# MCU.net
KiCad netlist of a schematic drawn in Altium Designer
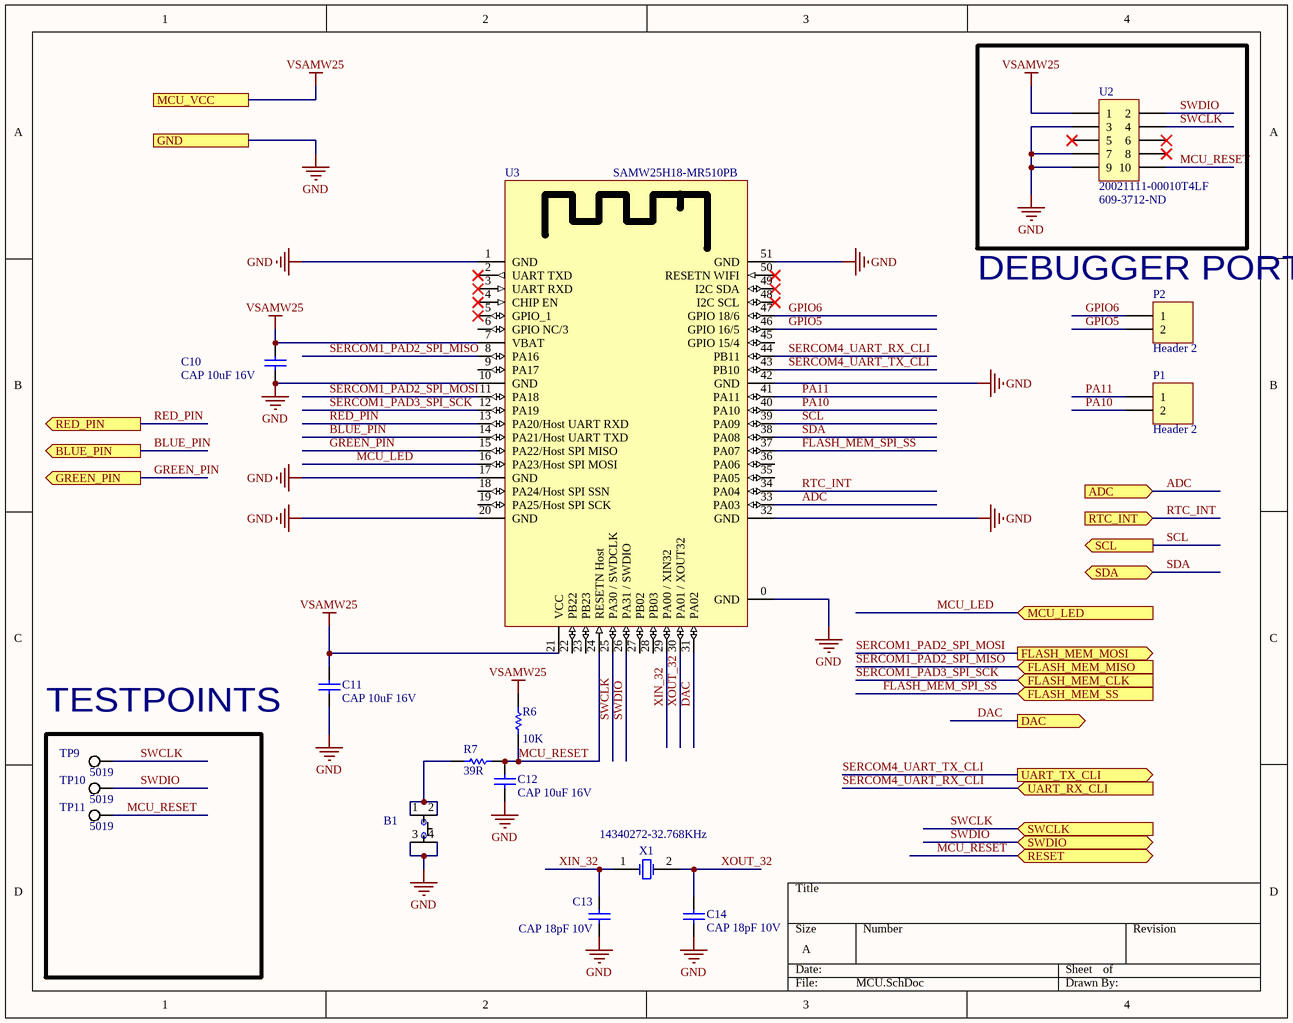
[diagram p0: MCU.SchDoc]

(export (version "E")
  (design (tool "Eeschema 10.0.6"))
  (components
    (comp (ref "B1")
      (value "PTS810 SJK 250 SMTR LFS")
      (footprint "PTS810 SJK 250 SMTR LFS")
      (description "SWITCH TACTILE SPST-NO 0.05A 16V Tactile Switch SPST-NO Top Actuated Surface Mount")
      (fields
        (field (name "MANUFACTURER") "ITT /  C&K Components")
        (field (name "MANUFACTURER PART NUMBER") "PTS810SJK250SMTRLFS")
      )
      (libsource (lib "Schematics") (part "PTS810 SJK 250 SMTR LFS"))
    )
    (comp (ref "C10")
      (value "CAP 10uF 16V")
      (footprint "CAPC0805(2012)145_L")
      (description "CAP 10uF 16V ±10% 0805 (2012 Metric) Thickness 1.45mm SMD")
      (fields (field (name "TOLERANCE") "Â±10%"))
      (libsource (lib "Altium Content Vault") (part "CAP"))
    )
    (comp (ref "C11")
      (value "CAP 10uF 16V")
      (footprint "CAPC0805(2012)145_L")
      (description "CAP 10uF 16V ±10% 0805 (2012 Metric) Thickness 1.45mm SMD")
      (fields (field (name "TOLERANCE") "Â±10%"))
      (libsource (lib "Altium Content Vault") (part "CAP"))
    )
    (comp (ref "C12")
      (value "CAP 10uF 16V")
      (footprint "CAPC0805(2012)145_L")
      (description "CAP 10uF 16V ±10% 0805 (2012 Metric) Thickness 1.45mm SMD")
      (fields (field (name "TOLERANCE") "Â±10%"))
      (libsource (lib "Altium Content Vault") (part "CAP"))
    )
    (comp (ref "C13")
      (value "CAP 18pF 10V")
      (footprint "CAPC0805(2012)75_L")
      (description "CAP 18pF 10V ±1% 0805 (2012 Metric) Thickness 0.75mm SMD")
      (fields (field (name "TOLERANCE") "Â±1%"))
      (libsource (lib "Altium Content Vault") (part "CAP"))
    )
    (comp (ref "C14")
      (value "CAP 18pF 10V")
      (footprint "CAPC0805(2012)75_L")
      (description "CAP 18pF 10V ±1% 0805 (2012 Metric) Thickness 0.75mm SMD")
      (fields (field (name "TOLERANCE") "Â±1%"))
      (libsource (lib "Altium Content Vault") (part "CAP"))
    )
    (comp (ref "P1")
      (value "Header 2")
      (footprint "HDR1X2")
      (description "Header, 2-Pin")
      (fields (field (name "PUBLISHER") "Altium Limited"))
      (libsource (lib "Miscellaneous Connectors") (part "Header 2"))
    )
    (comp (ref "P2")
      (value "Header 2")
      (footprint "HDR1X2")
      (description "Header, 2-Pin")
      (fields (field (name "PUBLISHER") "Altium Limited"))
      (libsource (lib "Miscellaneous Connectors") (part "Header 2"))
    )
    (comp (ref "R6")
      (value "10K")
      (footprint "J1-0603")
      (description "Resistor")
      (fields (field (name "PUBLISHER") "Altium Limited"))
      (libsource (lib "Miscellaneous Devices") (part "Res1"))
    )
    (comp (ref "R7")
      (value "39R")
      (footprint "RESC0805(2012)_N")
      (description "39R 0.125W 5% 0805 (2012 Metric)  SMD")
      (fields (field (name "POWER") "0.125 W") (field (name "TOLERANCE") "5 %"))
      (libsource (lib "Altium Content Vault") (part "RES"))
    )
    (comp (ref "TP9")
      (value "5019")
      (footprint "KSTN-5019_V")
      (description "Test Point, 1 Position SMD, RoHS, Tape and Reel")
      (libsource (lib "Altium Content Vault") (part "TESTPOINT_WHITE"))
    )
    (comp (ref "TP10")
      (value "5019")
      (footprint "KSTN-5019_V")
      (description "Test Point, 1 Position SMD, RoHS, Tape and Reel")
      (libsource (lib "Altium Content Vault") (part "TESTPOINT_WHITE"))
    )
    (comp (ref "TP11")
      (value "5019")
      (footprint "KSTN-5019_V")
      (description "Test Point, 1 Position SMD, RoHS, Tape and Reel")
      (libsource (lib "Altium Content Vault") (part "TESTPOINT_WHITE"))
    )
    (comp (ref "U2")
      (value "20021111-00010T4LF")
      (footprint "20021111-00010T4LF")
      (description "CONN HEADER 10POS UNSHD VERT T/H")
      (fields
        (field (name "MANUFACTURER") "Amphenol / FCI")
        (field (name "SUPPLIER PART NUMBER 1") "609-3712-ND")
      )
      (libsource (lib "Schematics") (part "20021111-00010T4LF"))
    )
    (comp (ref "U3")
      (value "SAMW25H18-MR510PB")
      (footprint "SAMW25H18-MR510PB")
      (description "RF TXRX MODULE WIFI TRACE ANT")
      (fields
        (field (name "MANUFACTURER") "Atmel")
        (field (name "MANUFACTURER PART NUMBER") "ATSAMW25H18-MR510PB")
      )
      (libsource (lib "Schematics") (part "SAMW25H18-MR510PB"))
    )
    (comp (ref "X1")
      (value "14340272-32.768KHz")
      (footprint "ITTI-14340272-32.768KHz-2_V")
      (description "Crystal, 32.768 KHz, -40 to 85 degC, 3.2 x 1.5 x 0.9 mm SMD")
      (fields (field (name "MANUFACTURER") "ITTI"))
      (libsource (lib "Altium Content Vault") (part "ITTI-14340272-2"))
    )
  )
  (nets
    (net (code "1") (name "/ADC") (class "Default")
      (node (ref "U3") (pin "33") (pinfunction "PA03_33") (pintype "bidirectional"))
    )
    (net (code "2") (name "/BLUE_PIN") (class "Default")
      (node (ref "U3") (pin "14") (pinfunction "PA21/Host_UART_TXD_14") (pintype "bidirectional"))
    )
    (net (code "3") (name "/DAC") (class "Default")
      (node (ref "U3") (pin "31") (pinfunction "PA02_31") (pintype "bidirectional"))
    )
    (net (code "4") (name "/FLASH_MEM_SPI_SS") (class "Default")
      (node (ref "U3") (pin "37") (pinfunction "PA07_37") (pintype "bidirectional"))
    )
    (net (code "5") (name "/GPIO5") (class "Default")
      (node (ref "P2") (pin "2") (pinfunction "2_2") (pintype "passive"))
      (node (ref "U3") (pin "46") (pinfunction "GPIO_16/5_46") (pintype "bidirectional"))
    )
    (net (code "6") (name "/GPIO6") (class "Default")
      (node (ref "P2") (pin "1") (pinfunction "1_1") (pintype "passive"))
      (node (ref "U3") (pin "47") (pinfunction "GPIO_18/6_47") (pintype "bidirectional"))
    )
    (net (code "7") (name "/GREEN_PIN") (class "Default")
      (node (ref "U3") (pin "15") (pinfunction "PA22/Host_SPI_MISO_15") (pintype "bidirectional"))
    )
    (net (code "8") (name "/MCU_LED") (class "Default")
      (node (ref "U3") (pin "16") (pinfunction "PA23/Host_SPI_MOSI_16") (pintype "bidirectional"))
    )
    (net (code "9") (name "/MCU_RESET") (class "Default")
      (node (ref "C12") (pin "2") (pinfunction "2_2") (pintype "passive"))
      (node (ref "R6") (pin "1") (pinfunction "1_1") (pintype "passive"))
      (node (ref "R7") (pin "1") (pinfunction "1_1") (pintype "passive"))
      (node (ref "TP11") (pin "1") (pinfunction "1_1") (pintype "passive"))
      (node (ref "U2") (pin "10") (pinfunction "10_10") (pintype "passive"))
      (node (ref "U3") (pin "24") (pinfunction "RESETN_Host_24") (pintype "input"))
    )
    (net (code "10") (name "/PA10") (class "Default")
      (node (ref "P1") (pin "2") (pinfunction "2_2") (pintype "passive"))
      (node (ref "U3") (pin "40") (pinfunction "PA10_40") (pintype "bidirectional"))
    )
    (net (code "11") (name "/PA11") (class "Default")
      (node (ref "P1") (pin "1") (pinfunction "1_1") (pintype "passive"))
      (node (ref "U3") (pin "41") (pinfunction "PA11_41") (pintype "bidirectional"))
    )
    (net (code "12") (name "/RED_PIN") (class "Default")
      (node (ref "U3") (pin "13") (pinfunction "PA20/Host_UART_RXD_13") (pintype "bidirectional"))
    )
    (net (code "13") (name "/RTC_INT") (class "Default")
      (node (ref "U3") (pin "34") (pinfunction "PA04_34") (pintype "bidirectional"))
    )
    (net (code "14") (name "/SCL") (class "Default")
      (node (ref "U3") (pin "39") (pinfunction "PA09_39") (pintype "bidirectional"))
    )
    (net (code "15") (name "/SDA") (class "Default")
      (node (ref "U3") (pin "38") (pinfunction "PA08_38") (pintype "bidirectional"))
    )
    (net (code "16") (name "/SERCOM1_PAD2_SPI_MISO") (class "Default")
      (node (ref "U3") (pin "8") (pinfunction "PA16_8") (pintype "bidirectional"))
    )
    (net (code "17") (name "/SERCOM1_PAD2_SPI_MOSI") (class "Default")
      (node (ref "U3") (pin "11") (pinfunction "PA18_11") (pintype "bidirectional"))
    )
    (net (code "18") (name "/SERCOM1_PAD3_SPI_SCK") (class "Default")
      (node (ref "U3") (pin "12") (pinfunction "PA19_12") (pintype "bidirectional"))
    )
    (net (code "19") (name "/SERCOM4_UART_RX_CLI") (class "Default")
      (node (ref "U3") (pin "44") (pinfunction "PB11_44") (pintype "bidirectional"))
    )
    (net (code "20") (name "/SERCOM4_UART_TX_CLI") (class "Default")
      (node (ref "U3") (pin "43") (pinfunction "PB10_43") (pintype "bidirectional"))
    )
    (net (code "21") (name "/SWCLK") (class "Default")
      (node (ref "TP9") (pin "1") (pinfunction "1_1") (pintype "passive"))
      (node (ref "U2") (pin "4") (pinfunction "4_4") (pintype "passive"))
      (node (ref "U3") (pin "25") (pinfunction "PA30_/_SWDCLK_25") (pintype "bidirectional"))
    )
    (net (code "22") (name "/SWDIO") (class "Default")
      (node (ref "TP10") (pin "1") (pinfunction "1_1") (pintype "passive"))
      (node (ref "U2") (pin "2") (pinfunction "2_2") (pintype "passive"))
      (node (ref "U3") (pin "26") (pinfunction "PA31_/_SWDIO_26") (pintype "bidirectional"))
    )
    (net (code "23") (name "/XIN_32") (class "Default")
      (node (ref "C13") (pin "1") (pinfunction "1_1") (pintype "passive"))
      (node (ref "U3") (pin "29") (pinfunction "PA00_/_XIN32_29") (pintype "bidirectional"))
      (node (ref "X1") (pin "1") (pinfunction "X1_1") (pintype "passive"))
    )
    (net (code "24") (name "/XOUT_32") (class "Default")
      (node (ref "C14") (pin "1") (pinfunction "1_1") (pintype "passive"))
      (node (ref "U3") (pin "30") (pinfunction "PA01_/_XOUT32_30") (pintype "bidirectional"))
      (node (ref "X1") (pin "2") (pinfunction "X2_2") (pintype "passive"))
    )
    (net (code "25") (name "GND") (class "Default")
      (node (ref "B1") (pin "3") (pinfunction "3_3") (pintype "power_in"))
      (node (ref "B1") (pin "4") (pinfunction "4_4") (pintype "power_in"))
      (node (ref "C10") (pin "1") (pinfunction "1_1") (pintype "passive"))
      (node (ref "C11") (pin "1") (pinfunction "1_1") (pintype "passive"))
      (node (ref "C12") (pin "1") (pinfunction "1_1") (pintype "passive"))
      (node (ref "C13") (pin "2") (pinfunction "2_2") (pintype "passive"))
      (node (ref "C14") (pin "2") (pinfunction "2_2") (pintype "passive"))
      (node (ref "U2") (pin "3") (pinfunction "3_3") (pintype "passive"))
      (node (ref "U2") (pin "7") (pinfunction "7_7") (pintype "passive"))
      (node (ref "U2") (pin "9") (pinfunction "9_9") (pintype "passive"))
      (node (ref "U3") (pin "0") (pinfunction "GND_0") (pintype "power_in"))
      (node (ref "U3") (pin "1") (pinfunction "GND_1") (pintype "power_in"))
      (node (ref "U3") (pin "10") (pinfunction "GND_10") (pintype "power_in"))
      (node (ref "U3") (pin "17") (pinfunction "GND_17") (pintype "power_in"))
      (node (ref "U3") (pin "20") (pinfunction "GND_20") (pintype "power_in"))
      (node (ref "U3") (pin "32") (pinfunction "GND_32") (pintype "power_in"))
      (node (ref "U3") (pin "42") (pinfunction "GND_42") (pintype "power_in"))
      (node (ref "U3") (pin "51") (pinfunction "GND_51") (pintype "power_in"))
    )
    (net (code "26") (name "Net-(B1-Pad1)") (class "Default")
      (node (ref "B1") (pin "1") (pinfunction "1_1") (pintype "power_in"))
      (node (ref "B1") (pin "2") (pinfunction "2_2") (pintype "power_in"))
      (node (ref "R7") (pin "2") (pinfunction "2_2") (pintype "passive"))
    )
    (net (code "27") (name "VSAMW25") (class "Default")
      (node (ref "C10") (pin "2") (pinfunction "2_2") (pintype "passive"))
      (node (ref "C11") (pin "2") (pinfunction "2_2") (pintype "passive"))
      (node (ref "R6") (pin "2") (pinfunction "2_2") (pintype "passive"))
      (node (ref "U2") (pin "1") (pinfunction "1_1") (pintype "passive"))
      (node (ref "U3") (pin "21") (pinfunction "VCC_21") (pintype "power_in"))
      (node (ref "U3") (pin "7") (pinfunction "VBAT_7") (pintype "power_in"))
    )
    (net (code "28") (name "unconnected-(U2-Pad5)") (class "Default")
      (node (ref "U2") (pin "5") (pinfunction "5_5") (pintype "passive+no_connect"))
    )
    (net (code "29") (name "unconnected-(U2-Pad6)") (class "Default")
      (node (ref "U2") (pin "6") (pinfunction "6_6") (pintype "passive+no_connect"))
    )
    (net (code "30") (name "unconnected-(U2-Pad8)") (class "Default")
      (node (ref "U2") (pin "8") (pinfunction "8_8") (pintype "passive+no_connect"))
    )
    (net (code "31") (name "unconnected-(U3-CHIP_EN-Pad4)") (class "Default")
      (node (ref "U3") (pin "4") (pinfunction "CHIP_EN_4") (pintype "input+no_connect"))
    )
    (net (code "32") (name "unconnected-(U3-GPIO_1-Pad5)") (class "Default")
      (node (ref "U3") (pin "5") (pinfunction "GPIO_1_5") (pintype "bidirectional+no_connect"))
    )
    (net (code "33") (name "unconnected-(U3-GPIO_15{slash}4-Pad45)") (class "Default")
      (node (ref "U3") (pin "45") (pinfunction "GPIO_15/4_45") (pintype "bidirectional"))
    )
    (net (code "34") (name "unconnected-(U3-GPIO_NC{slash}3-Pad6)") (class "Default")
      (node (ref "U3") (pin "6") (pinfunction "GPIO_NC/3_6") (pintype "bidirectional"))
    )
    (net (code "35") (name "unconnected-(U3-I2C_SCL-Pad48)") (class "Default")
      (node (ref "U3") (pin "48") (pinfunction "I2C_SCL_48") (pintype "bidirectional+no_connect"))
    )
    (net (code "36") (name "unconnected-(U3-I2C_SDA-Pad49)") (class "Default")
      (node (ref "U3") (pin "49") (pinfunction "I2C_SDA_49") (pintype "bidirectional+no_connect"))
    )
    (net (code "37") (name "unconnected-(U3-PA05-Pad35)") (class "Default")
      (node (ref "U3") (pin "35") (pinfunction "PA05_35") (pintype "bidirectional"))
    )
    (net (code "38") (name "unconnected-(U3-PA06-Pad36)") (class "Default")
      (node (ref "U3") (pin "36") (pinfunction "PA06_36") (pintype "bidirectional"))
    )
    (net (code "39") (name "unconnected-(U3-PA17-Pad9)") (class "Default")
      (node (ref "U3") (pin "9") (pinfunction "PA17_9") (pintype "bidirectional"))
    )
    (net (code "40") (name "unconnected-(U3-PA24{slash}Host_SPI_SSN-Pad18)") (class "Default")
      (node (ref "U3") (pin "18") (pinfunction "PA24/Host_SPI_SSN_18") (pintype "bidirectional"))
    )
    (net (code "41") (name "unconnected-(U3-PA25{slash}Host_SPI_SCK-Pad19)") (class "Default")
      (node (ref "U3") (pin "19") (pinfunction "PA25/Host_SPI_SCK_19") (pintype "bidirectional"))
    )
    (net (code "42") (name "unconnected-(U3-PB02-Pad27)") (class "Default")
      (node (ref "U3") (pin "27") (pinfunction "PB02_27") (pintype "bidirectional"))
    )
    (net (code "43") (name "unconnected-(U3-PB03-Pad28)") (class "Default")
      (node (ref "U3") (pin "28") (pinfunction "PB03_28") (pintype "bidirectional"))
    )
    (net (code "44") (name "unconnected-(U3-PB22-Pad22)") (class "Default")
      (node (ref "U3") (pin "22") (pinfunction "PB22_22") (pintype "bidirectional"))
    )
    (net (code "45") (name "unconnected-(U3-PB23-Pad23)") (class "Default")
      (node (ref "U3") (pin "23") (pinfunction "PB23_23") (pintype "bidirectional"))
    )
    (net (code "46") (name "unconnected-(U3-RESETN_WIFI-Pad50)") (class "Default")
      (node (ref "U3") (pin "50") (pinfunction "RESETN_WIFI_50") (pintype "input+no_connect"))
    )
    (net (code "47") (name "unconnected-(U3-UART_RXD-Pad3)") (class "Default")
      (node (ref "U3") (pin "3") (pinfunction "UART_RXD_3") (pintype "input+no_connect"))
    )
    (net (code "48") (name "unconnected-(U3-UART_TXD-Pad2)") (class "Default")
      (node (ref "U3") (pin "2") (pinfunction "UART_TXD_2") (pintype "output+no_connect"))
    )
  )
)
